# HeadphoneSlice.net
KiCad netlist of a schematic drawn in EAGLE
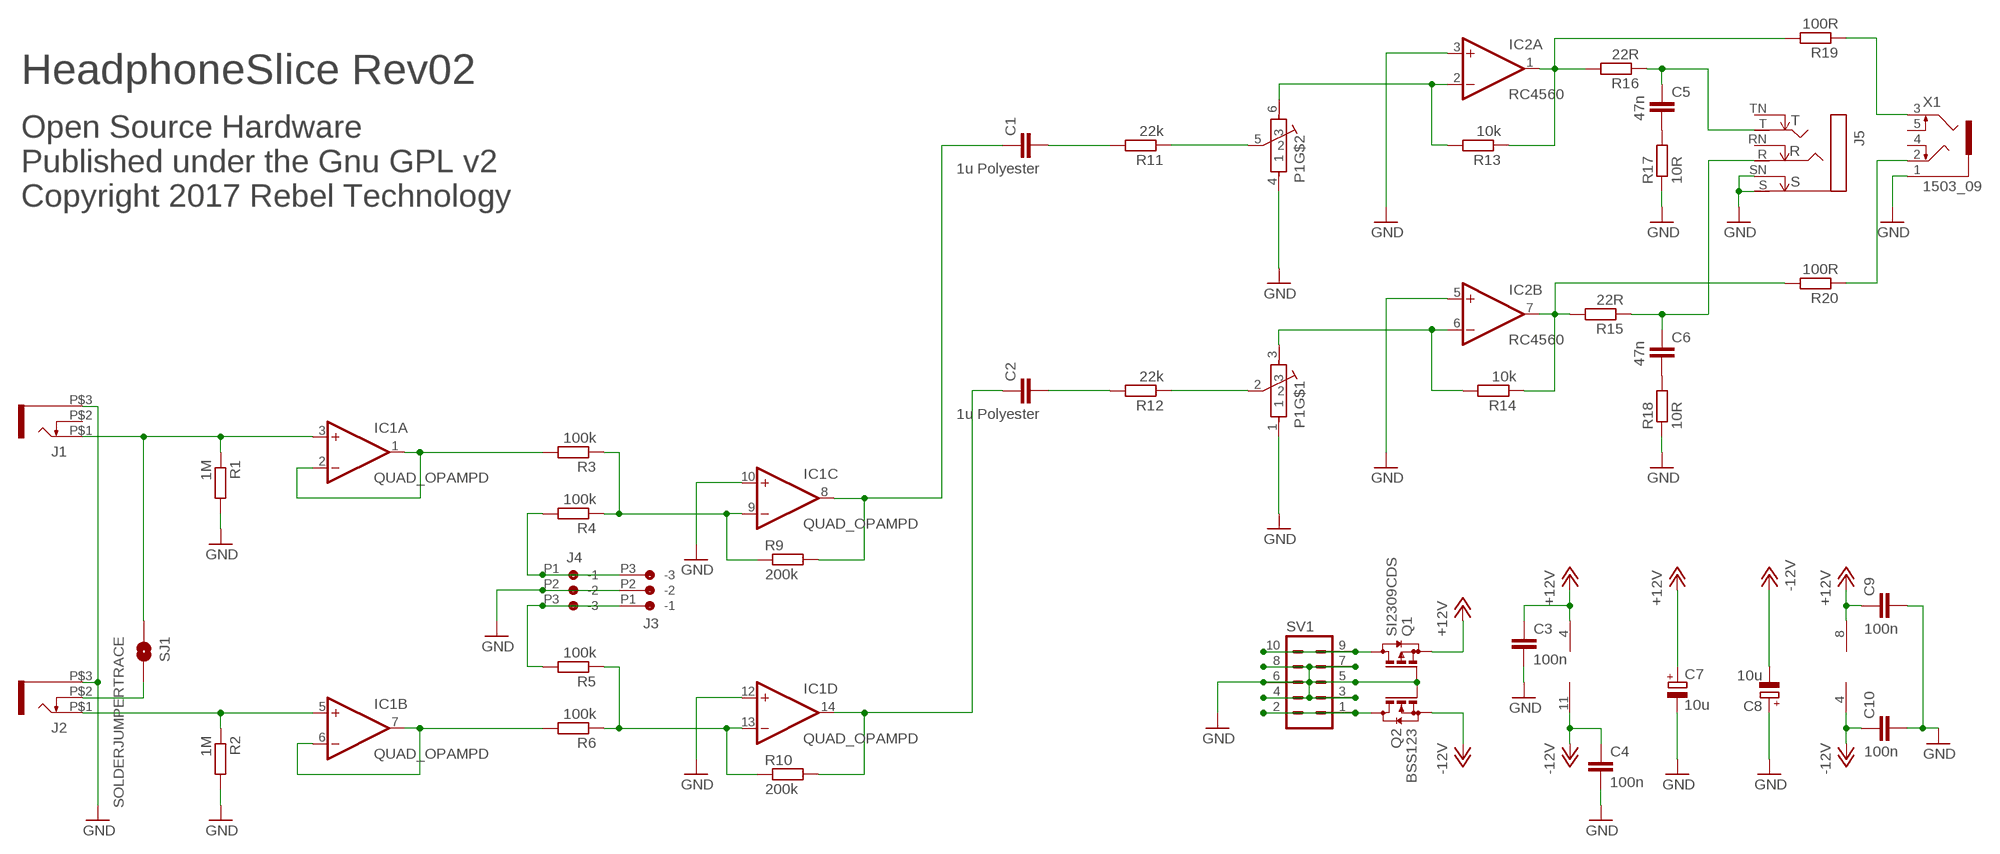
[diagram p0: schematic, sheet 1]

(export (version "E")
  (design (tool "Eeschema 10.0.6"))
  (components
    (comp (ref "C1")
      (value "1u Polyester")
      (footprint "eagle-import:C1210")
      (libsource (lib "eagle-import") (part "C-EUC1210"))
    )
    (comp (ref "C2")
      (value "1u Polyester")
      (footprint "eagle-import:C1210")
      (libsource (lib "eagle-import") (part "C-EUC1210"))
    )
    (comp (ref "C3")
      (value "100n")
      (footprint "eagle-import:C0603")
      (libsource (lib "eagle-import") (part "C-EUC0603"))
    )
    (comp (ref "C4")
      (value "100n")
      (footprint "eagle-import:C0603")
      (libsource (lib "eagle-import") (part "C-EUC0603"))
    )
    (comp (ref "C5")
      (value "47n")
      (footprint "eagle-import:C0603")
      (libsource (lib "eagle-import") (part "C-EUC0603"))
    )
    (comp (ref "C6")
      (value "47n")
      (footprint "eagle-import:C0603")
      (libsource (lib "eagle-import") (part "C-EUC0603"))
    )
    (comp (ref "C7")
      (value "10u")
      (footprint "eagle-import:153CLV-0505")
      (libsource (lib "eagle-import") (part "CPOL-EU153CLV-0505"))
    )
    (comp (ref "C8")
      (value "10u")
      (footprint "eagle-import:153CLV-0505")
      (libsource (lib "eagle-import") (part "CPOL-EU153CLV-0505"))
    )
    (comp (ref "C9")
      (value "100n")
      (footprint "eagle-import:C0603")
      (libsource (lib "eagle-import") (part "C-EUC0603"))
    )
    (comp (ref "C10")
      (value "100n")
      (footprint "eagle-import:C0603")
      (libsource (lib "eagle-import") (part "C-EUC0603"))
    )
    (comp (ref "IC1")
      (value "QUAD_OPAMPD")
      (footprint "eagle-import:SO14")
      (libsource (lib "eagle-import") (part "QUAD_OPAMPD"))
    )
    (comp (ref "IC2")
      (value "RC4560")
      (footprint "eagle-import:SO08")
      (libsource (lib "eagle-import") (part "NE5532D"))
    )
    (comp (ref "J1")
      (value "JACK-UJ-3502-RSLOT")
      (footprint "eagle-import:UJ-3502-R-SLOT")
      (libsource (lib "eagle-import") (part "JACK-UJ-3502-RSLOT"))
    )
    (comp (ref "J2")
      (value "JACK-UJ-3502-RSLOT")
      (footprint "eagle-import:UJ-3502-R-SLOT")
      (libsource (lib "eagle-import") (part "JACK-UJ-3502-RSLOT"))
    )
    (comp (ref "J3")
      (value "CON-JST_PH_3W")
      (footprint "eagle-import:CON-JST_PH_3W")
      (libsource (lib "eagle-import") (part "CON-JST_PH_3W"))
    )
    (comp (ref "J4")
      (value "CON-JST_PH_3W")
      (footprint "eagle-import:CON-JST_PH_3W")
      (libsource (lib "eagle-import") (part "CON-JST_PH_3W"))
    )
    (comp (ref "J5")
      (value "NEUTRIK_NRJ6HFSTD")
      (footprint "eagle-import:NRJ6HF")
      (libsource (lib "eagle-import") (part "NEUTRIK_NRJ6HFSTD"))
    )
    (comp (ref "P1")
      (value "POT-BOURNS-PTD902")
      (footprint "eagle-import:POT-BOURNS-PTD902")
      (libsource (lib "eagle-import") (part "POT-BOURNS-PTD902"))
    )
    (comp (ref "Q1")
      (value "SI2309CDS")
      (footprint "eagle-import:SOT23")
      (libsource (lib "eagle-import") (part "BSS84"))
    )
    (comp (ref "Q2")
      (value "BSS123")
      (footprint "eagle-import:SOT23")
      (libsource (lib "eagle-import") (part "BSS123"))
    )
    (comp (ref "R1")
      (value "1M")
      (footprint "eagle-import:0603")
      (libsource (lib "eagle-import") (part "R-EU_0603"))
    )
    (comp (ref "R2")
      (value "1M")
      (footprint "eagle-import:0603")
      (libsource (lib "eagle-import") (part "R-EU_0603"))
    )
    (comp (ref "R3")
      (value "100k")
      (footprint "eagle-import:0603")
      (libsource (lib "eagle-import") (part "R-EU_0603"))
    )
    (comp (ref "R4")
      (value "100k")
      (footprint "eagle-import:0603")
      (libsource (lib "eagle-import") (part "R-EU_0603"))
    )
    (comp (ref "R5")
      (value "100k")
      (footprint "eagle-import:0603")
      (libsource (lib "eagle-import") (part "R-EU_0603"))
    )
    (comp (ref "R6")
      (value "100k")
      (footprint "eagle-import:0603")
      (libsource (lib "eagle-import") (part "R-EU_0603"))
    )
    (comp (ref "R9")
      (value "200k")
      (footprint "eagle-import:0603")
      (libsource (lib "eagle-import") (part "R-EU_0603"))
    )
    (comp (ref "R10")
      (value "200k")
      (footprint "eagle-import:0603")
      (libsource (lib "eagle-import") (part "R-EU_0603"))
    )
    (comp (ref "R11")
      (value "22k")
      (footprint "eagle-import:0603")
      (libsource (lib "eagle-import") (part "R-EU_0603"))
    )
    (comp (ref "R12")
      (value "22k")
      (footprint "eagle-import:0603")
      (libsource (lib "eagle-import") (part "R-EU_0603"))
    )
    (comp (ref "R13")
      (value "10k")
      (footprint "eagle-import:0603")
      (libsource (lib "eagle-import") (part "R-EU_0603"))
    )
    (comp (ref "R14")
      (value "10k")
      (footprint "eagle-import:0603")
      (libsource (lib "eagle-import") (part "R-EU_0603"))
    )
    (comp (ref "R15")
      (value "22R")
      (footprint "eagle-import:0603")
      (libsource (lib "eagle-import") (part "R-EU_0603"))
    )
    (comp (ref "R16")
      (value "22R")
      (footprint "eagle-import:0603")
      (libsource (lib "eagle-import") (part "R-EU_0603"))
    )
    (comp (ref "R17")
      (value "10R")
      (footprint "eagle-import:0603")
      (libsource (lib "eagle-import") (part "R-EU_0603"))
    )
    (comp (ref "R18")
      (value "10R")
      (footprint "eagle-import:0603")
      (libsource (lib "eagle-import") (part "R-EU_0603"))
    )
    (comp (ref "R19")
      (value "100R")
      (footprint "eagle-import:0603")
      (libsource (lib "eagle-import") (part "R-EU_0603"))
    )
    (comp (ref "R20")
      (value "100R")
      (footprint "eagle-import:0603")
      (libsource (lib "eagle-import") (part "R-EU_0603"))
    )
    (comp (ref "SJ1")
      (value "SOLDERJUMPERTRACE")
      (footprint "eagle-import:SJ_2S-TRACE")
      (libsource (lib "eagle-import") (part "SOLDERJUMPERTRACE"))
    )
    (comp (ref "SV1")
      (value "MA05-2")
      (footprint "eagle-import:MA05-2")
      (libsource (lib "eagle-import") (part "MA05-2"))
    )
    (comp (ref "X1")
      (value "1503_09")
      (footprint "eagle-import:1503_09")
      (libsource (lib "eagle-import") (part "1503_09"))
    )
  )
  (nets
    (net (code "1") (name "+12V") (class "Default")
      (node (ref "C3") (pin "1") (pinfunction "1_1") (pintype "passive"))
      (node (ref "C7") (pin "+") (pinfunction "+_+") (pintype "passive"))
      (node (ref "C9") (pin "1") (pinfunction "1_1") (pintype "passive"))
      (node (ref "IC1") (pin "4") (pinfunction "V+_4") (pintype "power_in"))
      (node (ref "IC2") (pin "8") (pinfunction "V+_8") (pintype "power_in"))
      (node (ref "Q1") (pin "2") (pinfunction "S_2") (pintype "passive"))
    )
    (net (code "2") (name "-12V") (class "Default")
      (node (ref "C10") (pin "1") (pinfunction "1_1") (pintype "passive"))
      (node (ref "C4") (pin "1") (pinfunction "1_1") (pintype "passive"))
      (node (ref "C8") (pin "-") (pinfunction "-_-") (pintype "passive"))
      (node (ref "IC1") (pin "11") (pinfunction "V-_11") (pintype "power_in"))
      (node (ref "IC2") (pin "4") (pinfunction "V-_4") (pintype "power_in"))
      (node (ref "Q2") (pin "2") (pinfunction "S_2") (pintype "passive"))
    )
    (net (code "3") (name "GND") (class "Default")
      (node (ref "C10") (pin "2") (pinfunction "2_2") (pintype "passive"))
      (node (ref "C3") (pin "2") (pinfunction "2_2") (pintype "passive"))
      (node (ref "C4") (pin "2") (pinfunction "2_2") (pintype "passive"))
      (node (ref "C7") (pin "-") (pinfunction "-_-") (pintype "passive"))
      (node (ref "C8") (pin "+") (pinfunction "+_+") (pintype "passive"))
      (node (ref "C9") (pin "2") (pinfunction "2_2") (pintype "passive"))
      (node (ref "IC1") (pin "10") (pinfunction "+IN_10") (pintype "input"))
      (node (ref "IC1") (pin "12") (pinfunction "+IN_12") (pintype "input"))
      (node (ref "IC2") (pin "3") (pinfunction "+IN_3") (pintype "input"))
      (node (ref "IC2") (pin "5") (pinfunction "+IN_5") (pintype "input"))
      (node (ref "J1") (pin "P$3") (pinfunction "SLEEVE_P$3") (pintype "passive"))
      (node (ref "J2") (pin "P$3") (pinfunction "SLEEVE_P$3") (pintype "passive"))
      (node (ref "J3") (pin "P2") (pinfunction "-2_P2") (pintype "bidirectional"))
      (node (ref "J4") (pin "P2") (pinfunction "-2_P2") (pintype "bidirectional"))
      (node (ref "J5") (pin "S") (pinfunction "S_S") (pintype "passive"))
      (node (ref "J5") (pin "SN") (pinfunction "SN_SN") (pintype "passive"))
      (node (ref "P1") (pin "1") (pinfunction "1_1") (pintype "bidirectional"))
      (node (ref "P1") (pin "4") (pinfunction "1_4") (pintype "bidirectional"))
      (node (ref "Q1") (pin "1") (pinfunction "G_1") (pintype "passive"))
      (node (ref "Q2") (pin "1") (pinfunction "G_1") (pintype "passive"))
      (node (ref "R1") (pin "2") (pinfunction "2_2") (pintype "passive"))
      (node (ref "R17") (pin "1") (pinfunction "1_1") (pintype "passive"))
      (node (ref "R18") (pin "1") (pinfunction "1_1") (pintype "passive"))
      (node (ref "R2") (pin "2") (pinfunction "2_2") (pintype "passive"))
      (node (ref "SV1") (pin "3") (pinfunction "3_3") (pintype "passive"))
      (node (ref "SV1") (pin "4") (pinfunction "4_4") (pintype "passive"))
      (node (ref "SV1") (pin "5") (pinfunction "5_5") (pintype "passive"))
      (node (ref "SV1") (pin "6") (pinfunction "6_6") (pintype "passive"))
      (node (ref "SV1") (pin "7") (pinfunction "7_7") (pintype "passive"))
      (node (ref "SV1") (pin "8") (pinfunction "8_8") (pintype "passive"))
      (node (ref "X1") (pin "1") (pinfunction "1_1") (pintype "passive"))
    )
    (net (code "4") (name "Net-(C1-Pad2)") (class "Default")
      (node (ref "C1") (pin "2") (pinfunction "2_2") (pintype "passive"))
      (node (ref "R11") (pin "2") (pinfunction "2_2") (pintype "passive"))
    )
    (net (code "5") (name "Net-(C2-Pad2)") (class "Default")
      (node (ref "C2") (pin "2") (pinfunction "2_2") (pintype "passive"))
      (node (ref "R12") (pin "2") (pinfunction "2_2") (pintype "passive"))
    )
    (net (code "6") (name "Net-(C5-Pad1)") (class "Default")
      (node (ref "C5") (pin "1") (pinfunction "1_1") (pintype "passive"))
      (node (ref "J5") (pin "T") (pinfunction "T_T") (pintype "passive"))
      (node (ref "R16") (pin "1") (pinfunction "1_1") (pintype "passive"))
    )
    (net (code "7") (name "Net-(C5-Pad2)") (class "Default")
      (node (ref "C5") (pin "2") (pinfunction "2_2") (pintype "passive"))
      (node (ref "R17") (pin "2") (pinfunction "2_2") (pintype "passive"))
    )
    (net (code "8") (name "Net-(C6-Pad1)") (class "Default")
      (node (ref "C6") (pin "1") (pinfunction "1_1") (pintype "passive"))
      (node (ref "J5") (pin "R") (pinfunction "R_R") (pintype "passive"))
      (node (ref "R15") (pin "1") (pinfunction "1_1") (pintype "passive"))
    )
    (net (code "9") (name "Net-(C6-Pad2)") (class "Default")
      (node (ref "C6") (pin "2") (pinfunction "2_2") (pintype "passive"))
      (node (ref "R18") (pin "2") (pinfunction "2_2") (pintype "passive"))
    )
    (net (code "10") (name "Net-(IC1A-+IN)") (class "Default")
      (node (ref "IC1") (pin "3") (pinfunction "+IN_3") (pintype "input"))
      (node (ref "J1") (pin "P$1") (pinfunction "TIP_P$1") (pintype "passive"))
      (node (ref "R1") (pin "1") (pinfunction "1_1") (pintype "passive"))
      (node (ref "SJ1") (pin "1") (pinfunction "1_1") (pintype "passive"))
    )
    (net (code "11") (name "Net-(IC1A--IN)") (class "Default")
      (node (ref "IC1") (pin "1") (pinfunction "OUT_1") (pintype "output"))
      (node (ref "IC1") (pin "2") (pinfunction "-IN_2") (pintype "input"))
      (node (ref "R3") (pin "2") (pinfunction "2_2") (pintype "passive"))
    )
    (net (code "12") (name "Net-(IC1B-+IN)") (class "Default")
      (node (ref "IC1") (pin "5") (pinfunction "+IN_5") (pintype "input"))
      (node (ref "J2") (pin "P$1") (pinfunction "TIP_P$1") (pintype "passive"))
      (node (ref "R2") (pin "1") (pinfunction "1_1") (pintype "passive"))
    )
    (net (code "13") (name "Net-(IC1B--IN)") (class "Default")
      (node (ref "IC1") (pin "6") (pinfunction "-IN_6") (pintype "input"))
      (node (ref "IC1") (pin "7") (pinfunction "OUT_7") (pintype "output"))
      (node (ref "R6") (pin "2") (pinfunction "2_2") (pintype "passive"))
    )
    (net (code "14") (name "Net-(IC1C--IN)") (class "Default")
      (node (ref "IC1") (pin "9") (pinfunction "-IN_9") (pintype "input"))
      (node (ref "R3") (pin "1") (pinfunction "1_1") (pintype "passive"))
      (node (ref "R4") (pin "1") (pinfunction "1_1") (pintype "passive"))
      (node (ref "R9") (pin "1") (pinfunction "1_1") (pintype "passive"))
    )
    (net (code "15") (name "Net-(IC1C-OUT)") (class "Default")
      (node (ref "C1") (pin "1") (pinfunction "1_1") (pintype "passive"))
      (node (ref "IC1") (pin "8") (pinfunction "OUT_8") (pintype "output"))
      (node (ref "R9") (pin "2") (pinfunction "2_2") (pintype "passive"))
    )
    (net (code "16") (name "Net-(IC1D--IN)") (class "Default")
      (node (ref "IC1") (pin "13") (pinfunction "-IN_13") (pintype "input"))
      (node (ref "R10") (pin "1") (pinfunction "1_1") (pintype "passive"))
      (node (ref "R5") (pin "1") (pinfunction "1_1") (pintype "passive"))
      (node (ref "R6") (pin "1") (pinfunction "1_1") (pintype "passive"))
    )
    (net (code "17") (name "Net-(IC1D-OUT)") (class "Default")
      (node (ref "C2") (pin "1") (pinfunction "1_1") (pintype "passive"))
      (node (ref "IC1") (pin "14") (pinfunction "OUT_14") (pintype "output"))
      (node (ref "R10") (pin "2") (pinfunction "2_2") (pintype "passive"))
    )
    (net (code "18") (name "Net-(IC2A--IN)") (class "Default")
      (node (ref "IC2") (pin "2") (pinfunction "-IN_2") (pintype "input"))
      (node (ref "P1") (pin "6") (pinfunction "3_6") (pintype "bidirectional"))
      (node (ref "R13") (pin "2") (pinfunction "2_2") (pintype "passive"))
    )
    (net (code "19") (name "Net-(IC2A-OUT)") (class "Default")
      (node (ref "IC2") (pin "1") (pinfunction "OUT_1") (pintype "output"))
      (node (ref "R13") (pin "1") (pinfunction "1_1") (pintype "passive"))
      (node (ref "R16") (pin "2") (pinfunction "2_2") (pintype "passive"))
      (node (ref "R19") (pin "2") (pinfunction "2_2") (pintype "passive"))
    )
    (net (code "20") (name "Net-(IC2B--IN)") (class "Default")
      (node (ref "IC2") (pin "6") (pinfunction "-IN_6") (pintype "input"))
      (node (ref "P1") (pin "3") (pinfunction "3_3") (pintype "bidirectional"))
      (node (ref "R14") (pin "2") (pinfunction "2_2") (pintype "passive"))
    )
    (net (code "21") (name "Net-(IC2B-OUT)") (class "Default")
      (node (ref "IC2") (pin "7") (pinfunction "OUT_7") (pintype "output"))
      (node (ref "R14") (pin "1") (pinfunction "1_1") (pintype "passive"))
      (node (ref "R15") (pin "2") (pinfunction "2_2") (pintype "passive"))
      (node (ref "R20") (pin "2") (pinfunction "2_2") (pintype "passive"))
    )
    (net (code "22") (name "Net-(J2-SW)") (class "Default")
      (node (ref "J2") (pin "P$2") (pinfunction "SW_P$2") (pintype "passive"))
      (node (ref "SJ1") (pin "2") (pinfunction "2_2") (pintype "passive"))
    )
    (net (code "23") (name "Net-(J3--1)") (class "Default")
      (node (ref "J3") (pin "P1") (pinfunction "-1_P1") (pintype "bidirectional"))
      (node (ref "J4") (pin "P3") (pinfunction "-3_P3") (pintype "bidirectional"))
      (node (ref "R5") (pin "2") (pinfunction "2_2") (pintype "passive"))
    )
    (net (code "24") (name "Net-(J3--3)") (class "Default")
      (node (ref "J3") (pin "P3") (pinfunction "-3_P3") (pintype "bidirectional"))
      (node (ref "J4") (pin "P1") (pinfunction "-1_P1") (pintype "bidirectional"))
      (node (ref "R4") (pin "2") (pinfunction "2_2") (pintype "passive"))
    )
    (net (code "25") (name "Net-(P1-Pad2)") (class "Default")
      (node (ref "P1") (pin "2") (pinfunction "2_2") (pintype "bidirectional"))
      (node (ref "R12") (pin "1") (pinfunction "1_1") (pintype "passive"))
    )
    (net (code "26") (name "Net-(P1B-2)") (class "Default")
      (node (ref "P1") (pin "5") (pinfunction "2_5") (pintype "bidirectional"))
      (node (ref "R11") (pin "1") (pinfunction "1_1") (pintype "passive"))
    )
    (net (code "27") (name "Net-(Q1-D)") (class "Default")
      (node (ref "Q1") (pin "3") (pinfunction "D_3") (pintype "passive"))
      (node (ref "SV1") (pin "10") (pinfunction "10_10") (pintype "passive"))
      (node (ref "SV1") (pin "9") (pinfunction "9_9") (pintype "passive"))
    )
    (net (code "28") (name "Net-(Q2-D)") (class "Default")
      (node (ref "Q2") (pin "3") (pinfunction "D_3") (pintype "passive"))
      (node (ref "SV1") (pin "1") (pinfunction "1_1") (pintype "passive"))
      (node (ref "SV1") (pin "2") (pinfunction "2_2") (pintype "passive"))
    )
    (net (code "29") (name "Net-(R19-Pad1)") (class "Default")
      (node (ref "R19") (pin "1") (pinfunction "1_1") (pintype "passive"))
      (node (ref "X1") (pin "3") (pinfunction "3_3") (pintype "passive"))
    )
    (net (code "30") (name "Net-(R20-Pad1)") (class "Default")
      (node (ref "R20") (pin "1") (pinfunction "1_1") (pintype "passive"))
      (node (ref "X1") (pin "2") (pinfunction "2_2") (pintype "passive"))
    )
    (net (code "31") (name "unconnected-(J1-SW-PadP$2)") (class "Default")
      (node (ref "J1") (pin "P$2") (pinfunction "SW_P$2") (pintype "passive"))
    )
    (net (code "32") (name "unconnected-(J5-PadRN)") (class "Default")
      (node (ref "J5") (pin "RN") (pinfunction "RN_RN") (pintype "passive"))
    )
    (net (code "33") (name "unconnected-(J5-PadTN)") (class "Default")
      (node (ref "J5") (pin "TN") (pinfunction "TN_TN") (pintype "passive"))
    )
    (net (code "34") (name "unconnected-(X1-Pad4)") (class "Default")
      (node (ref "X1") (pin "4") (pinfunction "4_4") (pintype "passive"))
    )
    (net (code "35") (name "unconnected-(X1-Pad5)") (class "Default")
      (node (ref "X1") (pin "5") (pinfunction "5_5") (pintype "passive"))
    )
  )
)
